# PiZero-RAK.net
KiCad netlist of a schematic drawn in EAGLE
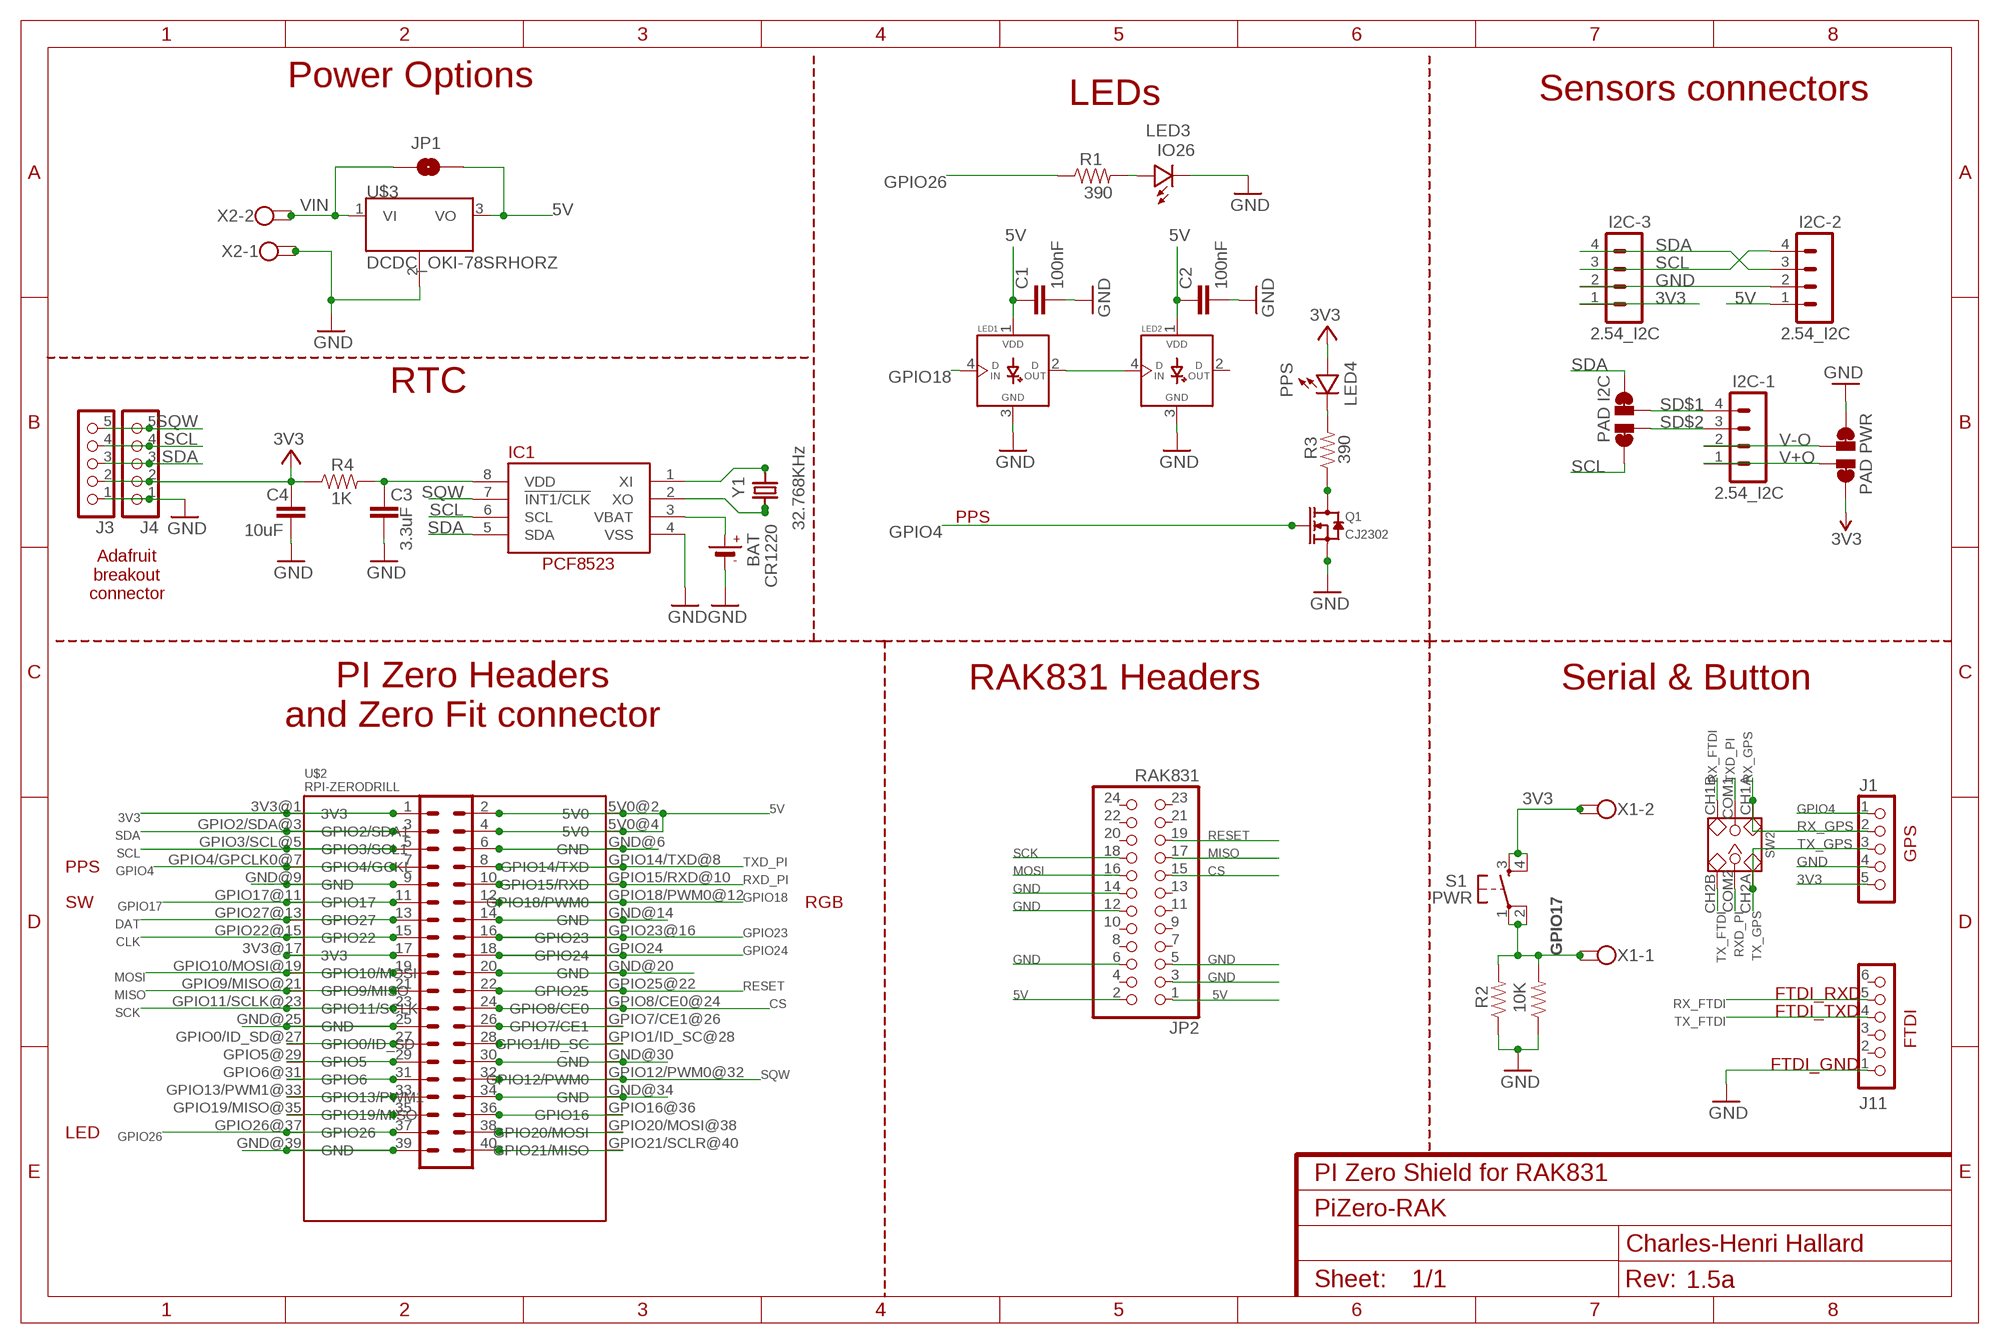
[diagram p0: schematic, sheet 1]

(export (version "E")
  (design (tool "Eeschema 10.0.6"))
  (components
    (comp (ref "BAT")
      (value "CR1220")
      (footprint "eagle-import:CR1220")
      (libsource (lib "eagle-import") (part "BATTERYCR1220_SMT"))
    )
    (comp (ref "C1")
      (value "100nF")
      (footprint "eagle-import:0805-CAP-LARGEPADS")
      (libsource (lib "eagle-import") (part "CAP0805-CAP-LARGEPADS"))
    )
    (comp (ref "C2")
      (value "100nF")
      (footprint "eagle-import:0805-CAP-LARGEPADS")
      (libsource (lib "eagle-import") (part "CAP0805-CAP-LARGEPADS"))
    )
    (comp (ref "C3")
      (value "3.3uF")
      (footprint "eagle-import:0805-CAP-LARGEPADS")
      (libsource (lib "eagle-import") (part "CAP0805-CAP-LARGEPADS"))
    )
    (comp (ref "C4")
      (value "10uF")
      (footprint "eagle-import:0805-CAP-LARGEPADS")
      (libsource (lib "eagle-import") (part "CAP0805-CAP-LARGEPADS"))
    )
    (comp (ref "I2C-1")
      (value "2.54_I2C")
      (footprint "eagle-import:1X04_NO_LOCK")
      (libsource (lib "eagle-import") (part "CON_HEADER_1X04'NO_LOCK'"))
    )
    (comp (ref "I2C-2")
      (value "2.54_I2C")
      (footprint "eagle-import:1X04_NO_LOCK")
      (libsource (lib "eagle-import") (part "CON_HEADER_1X04'NO_LOCK'"))
    )
    (comp (ref "I2C-3")
      (value "2.54_I2C")
      (footprint "eagle-import:1X04_NO_LOCK")
      (libsource (lib "eagle-import") (part "CON_HEADER_1X04'NO_LOCK'"))
    )
    (comp (ref "IC1")
      (value "PCF8523")
      (footprint "eagle-import:SOIC8_150MIL")
      (libsource (lib "eagle-import") (part "RTC_PCF8523T"))
    )
    (comp (ref "J1")
      (value "CON_HEADER_1X05-PTH")
      (footprint "eagle-import:M1X5")
      (libsource (lib "eagle-import") (part "CON_HEADER_1X05-PTH"))
    )
    (comp (ref "J2")
      (value "CONN_20X2HLE")
      (footprint "eagle-import:2X20-HLE")
      (libsource (lib "eagle-import") (part "CONN_20X2HLE"))
    )
    (comp (ref "J3")
      (value "CON_HEADER_1X05-PTH")
      (footprint "eagle-import:M1X5")
      (libsource (lib "eagle-import") (part "CON_HEADER_1X05-PTH"))
    )
    (comp (ref "J4")
      (value "CON_HEADER_1X05-PTH")
      (footprint "eagle-import:M1X5")
      (libsource (lib "eagle-import") (part "CON_HEADER_1X05-PTH"))
    )
    (comp (ref "J11")
      (value "CON_HEADER_1X06-PTH")
      (footprint "eagle-import:M1X6")
      (libsource (lib "eagle-import") (part "CON_HEADER_1X06-PTH"))
    )
    (comp (ref "JP1")
      (value "JUMPER-PAD-2-NOYES_SILK")
      (footprint "eagle-import:PAD-JUMPER-2-NO_YES_SILK")
      (libsource (lib "eagle-import") (part "JUMPER-PAD-2-NOYES_SILK"))
    )
    (comp (ref "JP2")
      (value "RAK831")
      (footprint "eagle-import:2X12")
      (libsource (lib "eagle-import") (part "PINHD-2X12"))
    )
    (comp (ref "LED1")
      (value "WS2812BLONG")
      (footprint "eagle-import:WS2812B-LONG")
      (libsource (lib "eagle-import") (part "WS2812BLONG"))
    )
    (comp (ref "LED2")
      (value "WS2812BLONG")
      (footprint "eagle-import:WS2812B-LONG")
      (libsource (lib "eagle-import") (part "WS2812BLONG"))
    )
    (comp (ref "LED3")
      (value "IO26")
      (footprint "eagle-import:0805-LED-LARGEPADS")
      (libsource (lib "eagle-import") (part "LED0805-LARGE"))
    )
    (comp (ref "LED4")
      (value "PPS")
      (footprint "eagle-import:0805-LED-LARGEPADS")
      (libsource (lib "eagle-import") (part "LED0805-LARGE"))
    )
    (comp (ref "Q1")
      (value "CJ2302")
      (footprint "eagle-import:SOT-23")
      (libsource (lib "eagle-import") (part "SMD-MOSFET-N-CH-20V-2.1A-CJ2302(SOT-23)"))
    )
    (comp (ref "R1")
      (value "390")
      (footprint "eagle-import:0805-RES")
      (libsource (lib "eagle-import") (part "RESISTOR0805-RES"))
    )
    (comp (ref "R2")
      (value "10K")
      (footprint "eagle-import:AXIAL-0.4")
      (libsource (lib "eagle-import") (part "RESISTORPTH-1/4W"))
    )
    (comp (ref "R3")
      (value "390")
      (footprint "eagle-import:0805-RES")
      (libsource (lib "eagle-import") (part "RESISTOR0805-RES"))
    )
    (comp (ref "R4")
      (value "1K")
      (footprint "eagle-import:0805-RES")
      (libsource (lib "eagle-import") (part "RESISTOR0805-RES"))
    )
    (comp (ref "R105")
      (value "RESISTOR0805-RES")
      (footprint "eagle-import:0805-RES")
      (libsource (lib "eagle-import") (part "RESISTOR0805-RES"))
    )
    (comp (ref "S1")
      (value "PWR")
      (footprint "eagle-import:TAC-SWITCH-PTH")
      (libsource (lib "eagle-import") (part "TACTILE-SWITCH-PTH"))
    )
    (comp (ref "SW2")
      (value "DIP-TOGGLE-SWITCH-2CH-(2X3P-2.54)")
      (footprint "eagle-import:SW6-2.54-9.0X3.5X3.2+2.0MM")
      (fields (field (name "MPN") "MS-22D18 G2 ROHS"))
      (libsource (lib "eagle-import") (part "DIP-TOGGLE-SWITCH-2CH-(2X3P-2.54)"))
    )
    (comp (ref "U$2")
      (value "RPI-ZERODRILL")
      (footprint "eagle-import:RPI-ZERO-DRILLS")
      (libsource (lib "eagle-import") (part "RPI-ZERODRILL"))
    )
    (comp (ref "U$3")
      (value "DCDC_OKI-78SRHORZ")
      (footprint "eagle-import:OKI-78SRH")
      (libsource (lib "eagle-import") (part "DCDC_OKI-78SRHORZ"))
    )
    (comp (ref "U$4")
      (value "PAD PWR")
      (footprint "eagle-import:PAD-JUMPER-SWAP")
      (libsource (lib "eagle-import") (part "PAD-JUMPER-SWAPSWAP"))
    )
    (comp (ref "U$5")
      (value "PAD I2C")
      (footprint "eagle-import:PAD-JUMPER-SWAP")
      (libsource (lib "eagle-import") (part "PAD-JUMPER-SWAPSWAP"))
    )
    (comp (ref "X1")
      (value "SPTAF_23.5")
      (footprint "eagle-import:FFKV2_35")
      (libsource (lib "eagle-import") (part "SPTAF_23.5"))
    )
    (comp (ref "X2")
      (value "SPTAF_25.0MM")
      (footprint "eagle-import:SPTAF_2X50")
      (libsource (lib "eagle-import") (part "SPTAF_25.0MM"))
    )
    (comp (ref "Y1")
      (value "32.768KHz")
      (footprint "eagle-import:TC26H")
      (libsource (lib "eagle-import") (part "CRYSTALTC26H"))
    )
    (comp (ref "Y2")
      (value "CRYSTAL8X3.8SMT")
      (footprint "eagle-import:CRYSTAL_8X3.8")
      (libsource (lib "eagle-import") (part "CRYSTAL8X3.8SMT"))
    )
  )
  (nets
    (net (code "1") (name "/SD$1") (class "Default")
      (node (ref "I2C-1") (pin "4") (pinfunction "4_4") (pintype "passive"))
      (node (ref "U$5") (pin "3") (pinfunction "3_3") (pintype "passive"))
    )
    (net (code "2") (name "/SD$2") (class "Default")
      (node (ref "I2C-1") (pin "3") (pinfunction "3_3") (pintype "passive"))
      (node (ref "U$5") (pin "2") (pinfunction "2_2") (pintype "passive"))
    )
    (net (code "3") (name "/V+O") (class "Default")
      (node (ref "I2C-1") (pin "1") (pinfunction "1_1") (pintype "passive"))
      (node (ref "U$4") (pin "3") (pinfunction "3_3") (pintype "passive"))
    )
    (net (code "4") (name "/V-O") (class "Default")
      (node (ref "I2C-1") (pin "2") (pinfunction "2_2") (pintype "passive"))
      (node (ref "U$4") (pin "2") (pinfunction "2_2") (pintype "passive"))
    )
    (net (code "5") (name "/VIN") (class "Default")
      (node (ref "JP1") (pin "1") (pinfunction "1_1") (pintype "passive"))
      (node (ref "U$3") (pin "1") (pinfunction "VI_1") (pintype "bidirectional"))
      (node (ref "X2") (pin "2") (pinfunction "1_2") (pintype "passive"))
      (node (ref "X2") (pin "2A") (pinfunction "2_2A") (pintype "passive"))
    )
    (net (code "6") (name "3V3") (class "Default")
      (node (ref "C4") (pin "1") (pinfunction "1_1") (pintype "passive"))
      (node (ref "I2C-3") (pin "1") (pinfunction "1_1") (pintype "passive"))
      (node (ref "J1") (pin "5") (pinfunction "5_5") (pintype "bidirectional"))
      (node (ref "J2") (pin "1") (pinfunction "1_1") (pintype "passive"))
      (node (ref "J3") (pin "2") (pinfunction "2_2") (pintype "bidirectional"))
      (node (ref "J4") (pin "2") (pinfunction "2_2") (pintype "bidirectional"))
      (node (ref "LED4") (pin "PLUS") (pinfunction "PLUS_PLUS") (pintype "passive"))
      (node (ref "R4") (pin "1") (pinfunction "1_1") (pintype "passive"))
      (node (ref "S1") (pin "3") (pinfunction "3_3") (pintype "passive"))
      (node (ref "S1") (pin "4") (pinfunction "4_4") (pintype "passive"))
      (node (ref "U$2") (pin "3V3@1") (pinfunction "3V3_3V3@1") (pintype "power_in"))
      (node (ref "U$4") (pin "4") (pinfunction "4_4") (pintype "passive"))
      (node (ref "U$4") (pin "44") (pinfunction "4_44") (pintype "passive"))
      (node (ref "X1") (pin "2") (pinfunction "1_2") (pintype "passive"))
      (node (ref "X1") (pin "2A") (pinfunction "2_2A") (pintype "passive"))
    )
    (net (code "7") (name "5V") (class "Default")
      (node (ref "C1") (pin "1") (pinfunction "1_1") (pintype "passive"))
      (node (ref "C2") (pin "1") (pinfunction "1_1") (pintype "passive"))
      (node (ref "I2C-2") (pin "1") (pinfunction "1_1") (pintype "passive"))
      (node (ref "J2") (pin "2") (pinfunction "2_2") (pintype "passive"))
      (node (ref "J2") (pin "4") (pinfunction "4_4") (pintype "passive"))
      (node (ref "JP1") (pin "2") (pinfunction "2_2") (pintype "passive"))
      (node (ref "JP2") (pin "1") (pinfunction "1_1") (pintype "passive"))
      (node (ref "JP2") (pin "2") (pinfunction "2_2") (pintype "passive"))
      (node (ref "LED1") (pin "1") (pinfunction "VDD_1") (pintype "power_in"))
      (node (ref "LED2") (pin "1") (pinfunction "VDD_1") (pintype "power_in"))
      (node (ref "U$2") (pin "5V0@2") (pinfunction "5V0_5V0@2") (pintype "power_in"))
      (node (ref "U$2") (pin "5V0@4") (pinfunction "5V0_5V0@4") (pintype "power_in"))
      (node (ref "U$3") (pin "3") (pinfunction "VO_3") (pintype "bidirectional"))
    )
    (net (code "8") (name "CLK") (class "Default")
      (node (ref "J2") (pin "15") (pinfunction "15_15") (pintype "passive"))
      (node (ref "U$2") (pin "GPIO22@15") (pinfunction "GPIO22_GPIO22@15") (pintype "bidirectional"))
    )
    (net (code "9") (name "CS") (class "Default")
      (node (ref "J2") (pin "24") (pinfunction "24_24") (pintype "passive"))
      (node (ref "JP2") (pin "15") (pinfunction "15_15") (pintype "passive"))
      (node (ref "U$2") (pin "GPIO8/CE0@24") (pinfunction "GPIO8/CE0_GPIO8/CE0@24") (pintype "bidirectional"))
    )
    (net (code "10") (name "DAT") (class "Default")
      (node (ref "J2") (pin "13") (pinfunction "13_13") (pintype "passive"))
      (node (ref "U$2") (pin "GPIO27@13") (pinfunction "GPIO27_GPIO27@13") (pintype "bidirectional"))
    )
    (net (code "11") (name "GND") (class "Default")
      (node (ref "BAT") (pin "-") (pinfunction "-_-") (pintype "passive"))
      (node (ref "C1") (pin "2") (pinfunction "2_2") (pintype "passive"))
      (node (ref "C2") (pin "2") (pinfunction "2_2") (pintype "passive"))
      (node (ref "C3") (pin "2") (pinfunction "2_2") (pintype "passive"))
      (node (ref "C4") (pin "2") (pinfunction "2_2") (pintype "passive"))
      (node (ref "I2C-2") (pin "2") (pinfunction "2_2") (pintype "passive"))
      (node (ref "I2C-3") (pin "2") (pinfunction "2_2") (pintype "passive"))
      (node (ref "IC1") (pin "4") (pinfunction "VSS_4") (pintype "power_in"))
      (node (ref "J1") (pin "4") (pinfunction "4_4") (pintype "bidirectional"))
      (node (ref "J11") (pin "1") (pinfunction "1_1") (pintype "bidirectional"))
      (node (ref "J2") (pin "14") (pinfunction "14_14") (pintype "passive"))
      (node (ref "J2") (pin "20") (pinfunction "20_20") (pintype "passive"))
      (node (ref "J2") (pin "25") (pinfunction "25_25") (pintype "passive"))
      (node (ref "J2") (pin "30") (pinfunction "30_30") (pintype "passive"))
      (node (ref "J2") (pin "34") (pinfunction "34_34") (pintype "passive"))
      (node (ref "J2") (pin "39") (pinfunction "39_39") (pintype "passive"))
      (node (ref "J2") (pin "6") (pinfunction "6_6") (pintype "passive"))
      (node (ref "J2") (pin "9") (pinfunction "9_9") (pintype "passive"))
      (node (ref "J3") (pin "1") (pinfunction "1_1") (pintype "bidirectional"))
      (node (ref "J4") (pin "1") (pinfunction "1_1") (pintype "bidirectional"))
      (node (ref "JP2") (pin "12") (pinfunction "12_12") (pintype "passive"))
      (node (ref "JP2") (pin "14") (pinfunction "14_14") (pintype "passive"))
      (node (ref "JP2") (pin "3") (pinfunction "3_3") (pintype "passive"))
      (node (ref "JP2") (pin "5") (pinfunction "5_5") (pintype "passive"))
      (node (ref "JP2") (pin "6") (pinfunction "6_6") (pintype "passive"))
      (node (ref "LED1") (pin "3") (pinfunction "GND_3") (pintype "power_in"))
      (node (ref "LED2") (pin "3") (pinfunction "GND_3") (pintype "power_in"))
      (node (ref "LED3") (pin "MINUS") (pinfunction "MINUS_MINUS") (pintype "passive"))
      (node (ref "Q1") (pin "2") (pinfunction "S_2") (pintype "passive"))
      (node (ref "R105") (pin "1") (pinfunction "1_1") (pintype "passive"))
      (node (ref "R2") (pin "P$1") (pinfunction "1_P$1") (pintype "passive"))
      (node (ref "U$2") (pin "GND@14") (pinfunction "GND_GND@14") (pintype "power_in"))
      (node (ref "U$2") (pin "GND@20") (pinfunction "GND_GND@20") (pintype "power_in"))
      (node (ref "U$2") (pin "GND@25") (pinfunction "GND_GND@25") (pintype "power_in"))
      (node (ref "U$2") (pin "GND@30") (pinfunction "GND_GND@30") (pintype "power_in"))
      (node (ref "U$2") (pin "GND@34") (pinfunction "GND_GND@34") (pintype "power_in"))
      (node (ref "U$2") (pin "GND@39") (pinfunction "GND_GND@39") (pintype "power_in"))
      (node (ref "U$2") (pin "GND@6") (pinfunction "GND_GND@6") (pintype "power_in"))
      (node (ref "U$2") (pin "GND@9") (pinfunction "GND_GND@9") (pintype "power_in"))
      (node (ref "U$3") (pin "2") (pinfunction "GND_2") (pintype "bidirectional"))
      (node (ref "U$4") (pin "1") (pinfunction "1_1") (pintype "passive"))
      (node (ref "U$4") (pin "11") (pinfunction "1_11") (pintype "passive"))
      (node (ref "X2") (pin "1") (pinfunction "1_1") (pintype "passive"))
      (node (ref "X2") (pin "1A") (pinfunction "2_1A") (pintype "passive"))
    )
    (net (code "12") (name "GPIO4") (class "Default")
      (node (ref "J1") (pin "1") (pinfunction "1_1") (pintype "bidirectional"))
      (node (ref "J2") (pin "7") (pinfunction "7_7") (pintype "passive"))
      (node (ref "Q1") (pin "1") (pinfunction "G_1") (pintype "passive"))
      (node (ref "U$2") (pin "GPIO4/GPCLK0@7") (pinfunction "GPIO4/GCKL_GPIO4/GPCLK0@7") (pintype "bidirectional"))
    )
    (net (code "13") (name "GPIO17") (class "Default")
      (node (ref "J2") (pin "11") (pinfunction "11_11") (pintype "passive"))
      (node (ref "R105") (pin "2") (pinfunction "2_2") (pintype "passive"))
      (node (ref "R2") (pin "P$2") (pinfunction "2_P$2") (pintype "passive"))
      (node (ref "S1") (pin "1") (pinfunction "1_1") (pintype "passive"))
      (node (ref "S1") (pin "2") (pinfunction "2_2") (pintype "passive"))
      (node (ref "U$2") (pin "GPIO17@11") (pinfunction "GPIO17_GPIO17@11") (pintype "bidirectional"))
      (node (ref "X1") (pin "1") (pinfunction "1_1") (pintype "passive"))
      (node (ref "X1") (pin "1A") (pinfunction "2_1A") (pintype "passive"))
    )
    (net (code "14") (name "GPIO18") (class "Default")
      (node (ref "J2") (pin "12") (pinfunction "12_12") (pintype "passive"))
      (node (ref "LED1") (pin "4") (pinfunction "DIN_4") (pintype "input"))
      (node (ref "U$2") (pin "GPIO18/PWM0@12") (pinfunction "GPIO18/PWM0_GPIO18/PWM0@12") (pintype "bidirectional"))
    )
    (net (code "15") (name "GPIO23") (class "Default")
      (node (ref "J2") (pin "16") (pinfunction "16_16") (pintype "passive"))
      (node (ref "U$2") (pin "GPIO23@16") (pinfunction "GPIO23_GPIO23@16") (pintype "bidirectional"))
    )
    (net (code "16") (name "GPIO24") (class "Default")
      (node (ref "J2") (pin "18") (pinfunction "18_18") (pintype "passive"))
      (node (ref "U$2") (pin "GPIO24") (pinfunction "GPIO24_GPIO24") (pintype "bidirectional"))
    )
    (net (code "17") (name "GPIO26") (class "Default")
      (node (ref "J2") (pin "37") (pinfunction "37_37") (pintype "passive"))
      (node (ref "R1") (pin "1") (pinfunction "1_1") (pintype "passive"))
      (node (ref "U$2") (pin "GPIO26@37") (pinfunction "GPIO26_GPIO26@37") (pintype "bidirectional"))
    )
    (net (code "18") (name "MISO") (class "Default")
      (node (ref "J2") (pin "21") (pinfunction "21_21") (pintype "passive"))
      (node (ref "JP2") (pin "17") (pinfunction "17_17") (pintype "passive"))
      (node (ref "U$2") (pin "GPIO9/MISO@21") (pinfunction "GPIO9/MISO_GPIO9/MISO@21") (pintype "bidirectional"))
    )
    (net (code "19") (name "MOSI") (class "Default")
      (node (ref "J2") (pin "19") (pinfunction "19_19") (pintype "passive"))
      (node (ref "JP2") (pin "16") (pinfunction "16_16") (pintype "passive"))
      (node (ref "U$2") (pin "GPIO10/MOSI@19") (pinfunction "GPIO10/MOSI_GPIO10/MOSI@19") (pintype "bidirectional"))
    )
    (net (code "20") (name "Net-(BAT-+)") (class "Default")
      (node (ref "BAT") (pin "+$1") (pinfunction "+_+$1") (pintype "passive"))
      (node (ref "IC1") (pin "3") (pinfunction "VBAT_3") (pintype "power_in"))
    )
    (net (code "21") (name "Net-(IC1-VDD)") (class "Default")
      (node (ref "C3") (pin "1") (pinfunction "1_1") (pintype "passive"))
      (node (ref "IC1") (pin "8") (pinfunction "VDD_8") (pintype "power_in"))
      (node (ref "R4") (pin "2") (pinfunction "2_2") (pintype "passive"))
    )
    (net (code "22") (name "Net-(IC1-XI)") (class "Default")
      (node (ref "IC1") (pin "1") (pinfunction "XI_1") (pintype "input"))
      (node (ref "Y1") (pin "1") (pinfunction "1_1") (pintype "passive"))
      (node (ref "Y2") (pin "P$4") (pinfunction "2_P$4") (pintype "passive"))
    )
    (net (code "23") (name "Net-(IC1-XO)") (class "Default")
      (node (ref "IC1") (pin "2") (pinfunction "XO_2") (pintype "output"))
      (node (ref "Y1") (pin "2") (pinfunction "2_2") (pintype "passive"))
      (node (ref "Y2") (pin "P$1") (pinfunction "1_P$1") (pintype "passive"))
    )
    (net (code "24") (name "Net-(J2-Pad17)") (class "Default")
      (node (ref "J2") (pin "17") (pinfunction "17_17") (pintype "passive"))
      (node (ref "U$2") (pin "3V3@17") (pinfunction "3V3_3V3@17") (pintype "power_in"))
    )
    (net (code "25") (name "Net-(LED1-DOUT)") (class "Default")
      (node (ref "LED1") (pin "2") (pinfunction "DOUT_2") (pintype "output"))
      (node (ref "LED2") (pin "4") (pinfunction "DIN_4") (pintype "input"))
    )
    (net (code "26") (name "Net-(LED3-PadPLUS)") (class "Default")
      (node (ref "LED3") (pin "PLUS") (pinfunction "PLUS_PLUS") (pintype "passive"))
      (node (ref "R1") (pin "2") (pinfunction "2_2") (pintype "passive"))
    )
    (net (code "27") (name "Net-(LED4-PadMINUS)") (class "Default")
      (node (ref "LED4") (pin "MINUS") (pinfunction "MINUS_MINUS") (pintype "passive"))
      (node (ref "R3") (pin "2") (pinfunction "2_2") (pintype "passive"))
    )
    (net (code "28") (name "Net-(Q1-D)") (class "Default")
      (node (ref "Q1") (pin "3") (pinfunction "D_3") (pintype "passive"))
      (node (ref "R3") (pin "1") (pinfunction "1_1") (pintype "passive"))
    )
    (net (code "29") (name "Net-(U$2-GPIO0{slash}ID_SD)") (class "Default")
      (node (ref "J2") (pin "27") (pinfunction "27_27") (pintype "passive"))
      (node (ref "U$2") (pin "GPIO0/ID_SD@27") (pinfunction "GPIO0/ID_SD_GPIO0/ID_SD@27") (pintype "bidirectional"))
    )
    (net (code "30") (name "Net-(U$2-GPIO1{slash}ID_SC)") (class "Default")
      (node (ref "J2") (pin "28") (pinfunction "28_28") (pintype "passive"))
      (node (ref "U$2") (pin "GPIO1/ID_SC@28") (pinfunction "GPIO1/ID_SC_GPIO1/ID_SC@28") (pintype "bidirectional"))
    )
    (net (code "31") (name "Net-(U$2-GPIO5)") (class "Default")
      (node (ref "J2") (pin "29") (pinfunction "29_29") (pintype "passive"))
      (node (ref "U$2") (pin "GPIO5@29") (pinfunction "GPIO5_GPIO5@29") (pintype "bidirectional"))
    )
    (net (code "32") (name "Net-(U$2-GPIO6)") (class "Default")
      (node (ref "J2") (pin "31") (pinfunction "31_31") (pintype "passive"))
      (node (ref "U$2") (pin "GPIO6@31") (pinfunction "GPIO6_GPIO6@31") (pintype "bidirectional"))
    )
    (net (code "33") (name "Net-(U$2-GPIO7{slash}CE1)") (class "Default")
      (node (ref "J2") (pin "26") (pinfunction "26_26") (pintype "passive"))
      (node (ref "U$2") (pin "GPIO7/CE1@26") (pinfunction "GPIO7/CE1_GPIO7/CE1@26") (pintype "bidirectional"))
    )
    (net (code "34") (name "Net-(U$2-GPIO13{slash}PWM1)") (class "Default")
      (node (ref "J2") (pin "33") (pinfunction "33_33") (pintype "passive"))
      (node (ref "U$2") (pin "GPIO13/PWM1@33") (pinfunction "GPIO13/PWM1_GPIO13/PWM1@33") (pintype "bidirectional"))
    )
    (net (code "35") (name "Net-(U$2-GPIO16)") (class "Default")
      (node (ref "J2") (pin "36") (pinfunction "36_36") (pintype "passive"))
      (node (ref "U$2") (pin "GPIO16@36") (pinfunction "GPIO16_GPIO16@36") (pintype "bidirectional"))
    )
    (net (code "36") (name "Net-(U$2-GPIO19{slash}MISO)") (class "Default")
      (node (ref "J2") (pin "35") (pinfunction "35_35") (pintype "passive"))
      (node (ref "U$2") (pin "GPIO19/MISO@35") (pinfunction "GPIO19/MISO_GPIO19/MISO@35") (pintype "bidirectional"))
    )
    (net (code "37") (name "Net-(U$2-GPIO20{slash}MOSI)") (class "Default")
      (node (ref "J2") (pin "38") (pinfunction "38_38") (pintype "passive"))
      (node (ref "U$2") (pin "GPIO20/MOSI@38") (pinfunction "GPIO20/MOSI_GPIO20/MOSI@38") (pintype "bidirectional"))
    )
    (net (code "38") (name "Net-(U$2-GPIO21{slash}MISO)") (class "Default")
      (node (ref "J2") (pin "40") (pinfunction "40_40") (pintype "passive"))
      (node (ref "U$2") (pin "GPIO21/SCLR@40") (pinfunction "GPIO21/MISO_GPIO21/SCLR@40") (pintype "bidirectional"))
    )
    (net (code "39") (name "RESET") (class "Default")
      (node (ref "J2") (pin "22") (pinfunction "22_22") (pintype "passive"))
      (node (ref "JP2") (pin "19") (pinfunction "19_19") (pintype "passive"))
      (node (ref "U$2") (pin "GPIO25@22") (pinfunction "GPIO25_GPIO25@22") (pintype "bidirectional"))
    )
    (net (code "40") (name "RXD_PI") (class "Default")
      (node (ref "J2") (pin "10") (pinfunction "10_10") (pintype "passive"))
      (node (ref "SW2") (pin "COM2") (pinfunction "COM2_COM2") (pintype "bidirectional"))
      (node (ref "U$2") (pin "GPIO15/RXD@10") (pinfunction "GPIO15/RXD_GPIO15/RXD@10") (pintype "bidirectional"))
    )
    (net (code "41") (name "RX_FTDI") (class "Default")
      (node (ref "J11") (pin "5") (pinfunction "5_5") (pintype "passive"))
      (node (ref "SW2") (pin "CH1B") (pinfunction "CH1B_CH1B") (pintype "bidirectional"))
    )
    (net (code "42") (name "RX_GPS") (class "Default")
      (node (ref "J1") (pin "2") (pinfunction "2_2") (pintype "bidirectional"))
      (node (ref "SW2") (pin "CH1A") (pinfunction "CH1A_CH1A") (pintype "bidirectional"))
    )
    (net (code "43") (name "SCK") (class "Default")
      (node (ref "J2") (pin "23") (pinfunction "23_23") (pintype "passive"))
      (node (ref "JP2") (pin "18") (pinfunction "18_18") (pintype "passive"))
      (node (ref "U$2") (pin "GPIO11/SCLK@23") (pinfunction "GPIO11/SCLK_GPIO11/SCLK@23") (pintype "bidirectional"))
    )
    (net (code "44") (name "SCL") (class "Default")
      (node (ref "I2C-2") (pin "4") (pinfunction "4_4") (pintype "passive"))
      (node (ref "I2C-3") (pin "3") (pinfunction "3_3") (pintype "passive"))
      (node (ref "IC1") (pin "6") (pinfunction "SCL_6") (pintype "bidirectional"))
      (node (ref "J2") (pin "5") (pinfunction "5_5") (pintype "passive"))
      (node (ref "J3") (pin "4") (pinfunction "4_4") (pintype "bidirectional"))
      (node (ref "J4") (pin "4") (pinfunction "4_4") (pintype "bidirectional"))
      (node (ref "U$2") (pin "GPIO3/SCL@5") (pinfunction "GPIO3/SCL1_GPIO3/SCL@5") (pintype "bidirectional"))
      (node (ref "U$5") (pin "1") (pinfunction "1_1") (pintype "passive"))
      (node (ref "U$5") (pin "11") (pinfunction "1_11") (pintype "passive"))
    )
    (net (code "45") (name "SDA") (class "Default")
      (node (ref "I2C-2") (pin "3") (pinfunction "3_3") (pintype "passive"))
      (node (ref "I2C-3") (pin "4") (pinfunction "4_4") (pintype "passive"))
      (node (ref "IC1") (pin "5") (pinfunction "SDA_5") (pintype "bidirectional"))
      (node (ref "J2") (pin "3") (pinfunction "3_3") (pintype "passive"))
      (node (ref "J3") (pin "3") (pinfunction "3_3") (pintype "bidirectional"))
      (node (ref "J4") (pin "3") (pinfunction "3_3") (pintype "bidirectional"))
      (node (ref "U$2") (pin "GPIO2/SDA@3") (pinfunction "GPIO2/SDA1_GPIO2/SDA@3") (pintype "bidirectional"))
      (node (ref "U$5") (pin "4") (pinfunction "4_4") (pintype "passive"))
      (node (ref "U$5") (pin "44") (pinfunction "4_44") (pintype "passive"))
    )
    (net (code "46") (name "SQW") (class "Default")
      (node (ref "IC1") (pin "7") (pinfunction "~{INT1/CLK}_7") (pintype "output"))
      (node (ref "J2") (pin "32") (pinfunction "32_32") (pintype "passive"))
      (node (ref "J3") (pin "5") (pinfunction "5_5") (pintype "bidirectional"))
      (node (ref "J4") (pin "5") (pinfunction "5_5") (pintype "bidirectional"))
      (node (ref "U$2") (pin "GPIO12/PWM0@32") (pinfunction "GPIO12/PWM0_GPIO12/PWM0@32") (pintype "bidirectional"))
    )
    (net (code "47") (name "TXD_PI") (class "Default")
      (node (ref "J2") (pin "8") (pinfunction "8_8") (pintype "passive"))
      (node (ref "SW2") (pin "COM1") (pinfunction "COM1_COM1") (pintype "bidirectional"))
      (node (ref "U$2") (pin "GPIO14/TXD@8") (pinfunction "GPIO14/TXD_GPIO14/TXD@8") (pintype "bidirectional"))
    )
    (net (code "48") (name "TX_FTDI") (class "Default")
      (node (ref "J11") (pin "4") (pinfunction "4_4") (pintype "passive"))
      (node (ref "SW2") (pin "CH2B") (pinfunction "CH2B_CH2B") (pintype "bidirectional"))
    )
    (net (code "49") (name "TX_GPS") (class "Default")
      (node (ref "J1") (pin "3") (pinfunction "3_3") (pintype "bidirectional"))
      (node (ref "SW2") (pin "CH2A") (pinfunction "CH2A_CH2A") (pintype "bidirectional"))
    )
    (net (code "50") (name "unconnected-(J11-Pad2)") (class "Default")
      (node (ref "J11") (pin "2") (pinfunction "2_2") (pintype "bidirectional"))
    )
    (net (code "51") (name "unconnected-(J11-Pad3)") (class "Default")
      (node (ref "J11") (pin "3") (pinfunction "3_3") (pintype "passive"))
    )
    (net (code "52") (name "unconnected-(J11-Pad6)") (class "Default")
      (node (ref "J11") (pin "6") (pinfunction "6_6") (pintype "passive"))
    )
    (net (code "53") (name "unconnected-(JP2-Pad4)") (class "Default")
      (node (ref "JP2") (pin "4") (pinfunction "4_4") (pintype "passive"))
    )
    (net (code "54") (name "unconnected-(JP2-Pad7)") (class "Default")
      (node (ref "JP2") (pin "7") (pinfunction "7_7") (pintype "passive"))
    )
    (net (code "55") (name "unconnected-(JP2-Pad8)") (class "Default")
      (node (ref "JP2") (pin "8") (pinfunction "8_8") (pintype "passive"))
    )
    (net (code "56") (name "unconnected-(JP2-Pad9)") (class "Default")
      (node (ref "JP2") (pin "9") (pinfunction "9_9") (pintype "passive"))
    )
    (net (code "57") (name "unconnected-(JP2-Pad10)") (class "Default")
      (node (ref "JP2") (pin "10") (pinfunction "10_10") (pintype "passive"))
    )
    (net (code "58") (name "unconnected-(JP2-Pad11)") (class "Default")
      (node (ref "JP2") (pin "11") (pinfunction "11_11") (pintype "passive"))
    )
    (net (code "59") (name "unconnected-(JP2-Pad13)") (class "Default")
      (node (ref "JP2") (pin "13") (pinfunction "13_13") (pintype "passive"))
    )
    (net (code "60") (name "unconnected-(JP2-Pad20)") (class "Default")
      (node (ref "JP2") (pin "20") (pinfunction "20_20") (pintype "passive"))
    )
    (net (code "61") (name "unconnected-(JP2-Pad21)") (class "Default")
      (node (ref "JP2") (pin "21") (pinfunction "21_21") (pintype "passive"))
    )
    (net (code "62") (name "unconnected-(JP2-Pad22)") (class "Default")
      (node (ref "JP2") (pin "22") (pinfunction "22_22") (pintype "passive"))
    )
    (net (code "63") (name "unconnected-(JP2-Pad23)") (class "Default")
      (node (ref "JP2") (pin "23") (pinfunction "23_23") (pintype "passive"))
    )
    (net (code "64") (name "unconnected-(JP2-Pad24)") (class "Default")
      (node (ref "JP2") (pin "24") (pinfunction "24_24") (pintype "passive"))
    )
    (net (code "65") (name "unconnected-(LED2-DOUT-Pad2)") (class "Default")
      (node (ref "LED2") (pin "2") (pinfunction "DOUT_2") (pintype "output"))
    )
  )
)
